# StrainGuageNode.net
KiCad netlist of a schematic drawn in Altium Designer
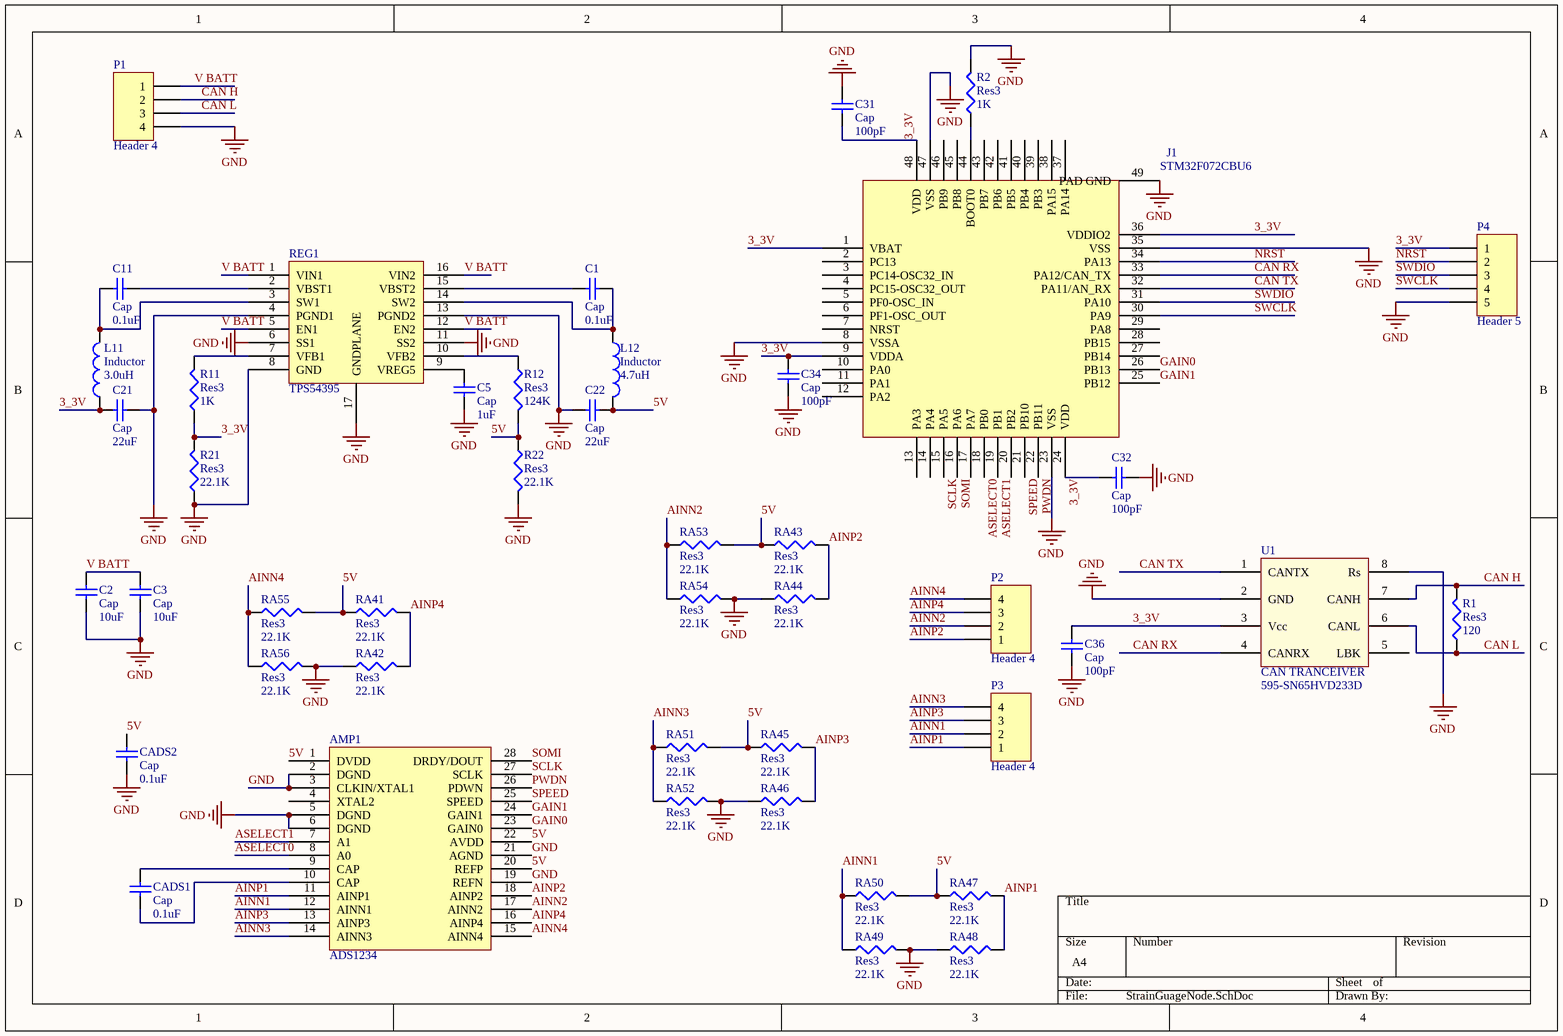
[diagram p0: StrainGuageNode.SchDoc]

(export (version "E")
  (design (tool "Eeschema 10.0.6"))
  (components
    (comp (ref "AMP1")
      (value "ADS1234")
      (footprint "ADS1234")
      (libsource (lib "StrainGaugeLib") (part "ADS1234"))
    )
    (comp (ref "C1")
      (value "Cap")
      (footprint "R0805")
      (description "Capacitor")
      (fields (field (name "ALTIUM_VALUE") "0.1uF") (field (name "PUBLISHER") "Altium Limited"))
      (libsource (lib "Miscellaneous Devices") (part "Cap"))
    )
    (comp (ref "C2")
      (value "Cap")
      (footprint "R0805")
      (description "Capacitor")
      (fields (field (name "ALTIUM_VALUE") "10uF") (field (name "PUBLISHER") "Altium Limited"))
      (libsource (lib "Miscellaneous Devices") (part "Cap"))
    )
    (comp (ref "C3")
      (value "Cap")
      (footprint "R0805")
      (description "Capacitor")
      (fields (field (name "ALTIUM_VALUE") "10uF") (field (name "PUBLISHER") "Altium Limited"))
      (libsource (lib "Miscellaneous Devices") (part "Cap"))
    )
    (comp (ref "C5")
      (value "Cap")
      (footprint "R0805")
      (description "Capacitor")
      (fields (field (name "ALTIUM_VALUE") "1uF") (field (name "PUBLISHER") "Altium Limited"))
      (libsource (lib "Miscellaneous Devices") (part "Cap"))
    )
    (comp (ref "C11")
      (value "Cap")
      (footprint "R0805")
      (description "Capacitor")
      (fields (field (name "ALTIUM_VALUE") "0.1uF") (field (name "PUBLISHER") "Altium Limited"))
      (libsource (lib "Miscellaneous Devices") (part "Cap"))
    )
    (comp (ref "C21")
      (value "Cap")
      (footprint "R0805")
      (description "Capacitor")
      (fields (field (name "ALTIUM_VALUE") "22uF") (field (name "PUBLISHER") "Altium Limited"))
      (libsource (lib "Miscellaneous Devices") (part "Cap"))
    )
    (comp (ref "C22")
      (value "Cap")
      (footprint "R0805")
      (description "Capacitor")
      (fields (field (name "ALTIUM_VALUE") "22uF") (field (name "PUBLISHER") "Altium Limited"))
      (libsource (lib "Miscellaneous Devices") (part "Cap"))
    )
    (comp (ref "C31")
      (value "Cap")
      (footprint "R0805")
      (description "Capacitor")
      (fields (field (name "ALTIUM_VALUE") "100pF") (field (name "PUBLISHER") "Altium Limited"))
      (libsource (lib "Miscellaneous Devices") (part "Cap"))
    )
    (comp (ref "C32")
      (value "Cap")
      (footprint "R0805")
      (description "Capacitor")
      (fields (field (name "ALTIUM_VALUE") "100pF") (field (name "PUBLISHER") "Altium Limited"))
      (libsource (lib "Miscellaneous Devices") (part "Cap"))
    )
    (comp (ref "C34")
      (value "Cap")
      (footprint "R0805")
      (description "Capacitor")
      (fields (field (name "ALTIUM_VALUE") "100pF") (field (name "PUBLISHER") "Altium Limited"))
      (libsource (lib "Miscellaneous Devices") (part "Cap"))
    )
    (comp (ref "C36")
      (value "Cap")
      (footprint "R0805")
      (description "Capacitor")
      (fields (field (name "ALTIUM_VALUE") "100pF") (field (name "PUBLISHER") "Altium Limited"))
      (libsource (lib "Miscellaneous Devices") (part "Cap"))
    )
    (comp (ref "CADS1")
      (value "Cap")
      (footprint "R0805")
      (description "Capacitor")
      (fields (field (name "ALTIUM_VALUE") "0.1uF") (field (name "PUBLISHER") "Altium Limited"))
      (libsource (lib "Miscellaneous Devices") (part "Cap"))
    )
    (comp (ref "CADS2")
      (value "Cap")
      (footprint "R0805")
      (description "Capacitor")
      (fields (field (name "ALTIUM_VALUE") "0.1uF") (field (name "PUBLISHER") "Altium Limited"))
      (libsource (lib "Miscellaneous Devices") (part "Cap"))
    )
    (comp (ref "J1")
      (value "STM32F072CBU6")
      (footprint "STM32F072CBU6 - duplicate")
      (description "MICROCONTROLLER")
      (libsource (lib "CAN_Node") (part "STM32F072CBU6"))
    )
    (comp (ref "L11")
      (value "Inductor")
      (footprint "Inductor")
      (fields (field (name "ALTIUM_VALUE") "3.0uH") (field (name "PUBLISHER") "Altium Limited"))
      (libsource (lib "") (part "Inductor_1"))
    )
    (comp (ref "L12")
      (value "Inductor")
      (footprint "Inductor")
      (fields (field (name "ALTIUM_VALUE") "4.7uH") (field (name "PUBLISHER") "Altium Limited"))
      (libsource (lib "Miscellaneous Devices") (part "Inductor"))
    )
    (comp (ref "P1")
      (value "Header 4")
      (footprint "HDR1X4")
      (description "Header, 4-Pin")
      (fields (field (name "PUBLISHER") "Altium Limited"))
      (libsource (lib "") (part "Header 4_1"))
    )
    (comp (ref "P2")
      (value "Header 4")
      (footprint "HDR1X4")
      (description "Header, 4-Pin")
      (fields (field (name "PUBLISHER") "Altium Limited"))
      (libsource (lib "Miscellaneous Connectors") (part "Header 4"))
    )
    (comp (ref "P3")
      (value "Header 4")
      (footprint "HDR1X4")
      (description "Header, 4-Pin")
      (fields (field (name "PUBLISHER") "Altium Limited"))
      (libsource (lib "Miscellaneous Connectors") (part "Header 4"))
    )
    (comp (ref "P4")
      (value "Header 5")
      (footprint "HDR1X5")
      (description "Header, 5-Pin")
      (fields (field (name "PUBLISHER") "Altium Limited"))
      (libsource (lib "Miscellaneous Connectors") (part "Header 5"))
    )
    (comp (ref "R1")
      (value "Res3")
      (footprint "R0805")
      (description "Resistor")
      (fields (field (name "ALTIUM_VALUE") "120") (field (name "PUBLISHER") "Altium Limited"))
      (libsource (lib "Miscellaneous Devices") (part "Res3"))
    )
    (comp (ref "R2")
      (value "Res3")
      (footprint "R0805")
      (description "Resistor")
      (fields (field (name "ALTIUM_VALUE") "1K") (field (name "PUBLISHER") "Altium Limited"))
      (libsource (lib "Miscellaneous Devices") (part "Res3"))
    )
    (comp (ref "R11")
      (value "Res3")
      (footprint "R0805")
      (description "Resistor")
      (fields (field (name "ALTIUM_VALUE") "1K") (field (name "PUBLISHER") "Altium Limited"))
      (libsource (lib "Miscellaneous Devices") (part "Res3"))
    )
    (comp (ref "R12")
      (value "Res3")
      (footprint "R0805")
      (description "Resistor")
      (fields (field (name "ALTIUM_VALUE") "124K") (field (name "PUBLISHER") "Altium Limited"))
      (libsource (lib "Miscellaneous Devices") (part "Res3"))
    )
    (comp (ref "R21")
      (value "Res3")
      (footprint "R0805")
      (description "Resistor")
      (fields (field (name "ALTIUM_VALUE") "22.1K") (field (name "PUBLISHER") "Altium Limited"))
      (libsource (lib "Miscellaneous Devices") (part "Res3"))
    )
    (comp (ref "R22")
      (value "Res3")
      (footprint "R0805")
      (description "Resistor")
      (fields (field (name "ALTIUM_VALUE") "22.1K") (field (name "PUBLISHER") "Altium Limited"))
      (libsource (lib "Miscellaneous Devices") (part "Res3"))
    )
    (comp (ref "RA41")
      (value "Res3")
      (footprint "R0805")
      (description "Resistor")
      (fields (field (name "ALTIUM_VALUE") "22.1K") (field (name "PUBLISHER") "Altium Limited"))
      (libsource (lib "Miscellaneous Devices") (part "Res3"))
    )
    (comp (ref "RA42")
      (value "Res3")
      (footprint "R0805")
      (description "Resistor")
      (fields (field (name "ALTIUM_VALUE") "22.1K") (field (name "PUBLISHER") "Altium Limited"))
      (libsource (lib "Miscellaneous Devices") (part "Res3"))
    )
    (comp (ref "RA43")
      (value "Res3")
      (footprint "R0805")
      (description "Resistor")
      (fields (field (name "ALTIUM_VALUE") "22.1K") (field (name "PUBLISHER") "Altium Limited"))
      (libsource (lib "Miscellaneous Devices") (part "Res3"))
    )
    (comp (ref "RA44")
      (value "Res3")
      (footprint "R0805")
      (description "Resistor")
      (fields (field (name "ALTIUM_VALUE") "22.1K") (field (name "PUBLISHER") "Altium Limited"))
      (libsource (lib "Miscellaneous Devices") (part "Res3"))
    )
    (comp (ref "RA45")
      (value "Res3")
      (footprint "R0805")
      (description "Resistor")
      (fields (field (name "ALTIUM_VALUE") "22.1K") (field (name "PUBLISHER") "Altium Limited"))
      (libsource (lib "Miscellaneous Devices") (part "Res3"))
    )
    (comp (ref "RA46")
      (value "Res3")
      (footprint "R0805")
      (description "Resistor")
      (fields (field (name "ALTIUM_VALUE") "22.1K") (field (name "PUBLISHER") "Altium Limited"))
      (libsource (lib "Miscellaneous Devices") (part "Res3"))
    )
    (comp (ref "RA47")
      (value "Res3")
      (footprint "R0805")
      (description "Resistor")
      (fields (field (name "ALTIUM_VALUE") "22.1K") (field (name "PUBLISHER") "Altium Limited"))
      (libsource (lib "Miscellaneous Devices") (part "Res3"))
    )
    (comp (ref "RA48")
      (value "Res3")
      (footprint "R0805")
      (description "Resistor")
      (fields (field (name "ALTIUM_VALUE") "22.1K") (field (name "PUBLISHER") "Altium Limited"))
      (libsource (lib "Miscellaneous Devices") (part "Res3"))
    )
    (comp (ref "RA49")
      (value "Res3")
      (footprint "R0805")
      (description "Resistor")
      (fields (field (name "ALTIUM_VALUE") "22.1K") (field (name "PUBLISHER") "Altium Limited"))
      (libsource (lib "Miscellaneous Devices") (part "Res3"))
    )
    (comp (ref "RA50")
      (value "Res3")
      (footprint "R0805")
      (description "Resistor")
      (fields (field (name "ALTIUM_VALUE") "22.1K") (field (name "PUBLISHER") "Altium Limited"))
      (libsource (lib "Miscellaneous Devices") (part "Res3"))
    )
    (comp (ref "RA51")
      (value "Res3")
      (footprint "R0805")
      (description "Resistor")
      (fields (field (name "ALTIUM_VALUE") "22.1K") (field (name "PUBLISHER") "Altium Limited"))
      (libsource (lib "Miscellaneous Devices") (part "Res3"))
    )
    (comp (ref "RA52")
      (value "Res3")
      (footprint "R0805")
      (description "Resistor")
      (fields (field (name "ALTIUM_VALUE") "22.1K") (field (name "PUBLISHER") "Altium Limited"))
      (libsource (lib "Miscellaneous Devices") (part "Res3"))
    )
    (comp (ref "RA53")
      (value "Res3")
      (footprint "R0805")
      (description "Resistor")
      (fields (field (name "ALTIUM_VALUE") "22.1K") (field (name "PUBLISHER") "Altium Limited"))
      (libsource (lib "Miscellaneous Devices") (part "Res3"))
    )
    (comp (ref "RA54")
      (value "Res3")
      (footprint "R0805")
      (description "Resistor")
      (fields (field (name "ALTIUM_VALUE") "22.1K") (field (name "PUBLISHER") "Altium Limited"))
      (libsource (lib "Miscellaneous Devices") (part "Res3"))
    )
    (comp (ref "RA55")
      (value "Res3")
      (footprint "R0805")
      (description "Resistor")
      (fields (field (name "ALTIUM_VALUE") "22.1K") (field (name "PUBLISHER") "Altium Limited"))
      (libsource (lib "Miscellaneous Devices") (part "Res3"))
    )
    (comp (ref "RA56")
      (value "Res3")
      (footprint "R0805")
      (description "Resistor")
      (fields (field (name "ALTIUM_VALUE") "22.1K") (field (name "PUBLISHER") "Altium Limited"))
      (libsource (lib "Miscellaneous Devices") (part "Res3"))
    )
    (comp (ref "REG1")
      (value "TPS54395")
      (footprint "TPS54395")
      (description "Dual Channel Buck Converter")
      (libsource (lib "StrainGaugeLib") (part "TPS54395"))
    )
    (comp (ref "U1")
      (value "CAN TRANCEIVER")
      (footprint "SOP8")
      (fields (field (name "SUPPLIER PART NUMBER 1") "595-SN65HVD233D"))
      (libsource (lib "CAN_Node") (part "595-SN65HVD233"))
    )
  )
  (nets
    (net (code "1") (name "/3_3V") (class "Default")
      (node (ref "C21") (pin "2") (pinfunction "2_2") (pintype "passive"))
      (node (ref "C31") (pin "2") (pinfunction "2_2") (pintype "passive"))
      (node (ref "C32") (pin "2") (pinfunction "2_2") (pintype "passive"))
      (node (ref "C34") (pin "2") (pinfunction "2_2") (pintype "passive"))
      (node (ref "C36") (pin "2") (pinfunction "2_2") (pintype "passive"))
      (node (ref "J1") (pin "1") (pinfunction "VBAT_1") (pintype "passive"))
      (node (ref "J1") (pin "24") (pinfunction "VDD_24") (pintype "passive"))
      (node (ref "J1") (pin "36") (pinfunction "VDDIO2_36") (pintype "passive"))
      (node (ref "J1") (pin "48") (pinfunction "VDD_48") (pintype "passive"))
      (node (ref "J1") (pin "9") (pinfunction "VDDA_9") (pintype "passive"))
      (node (ref "L11") (pin "1") (pinfunction "1_1") (pintype "passive"))
      (node (ref "P4") (pin "1") (pinfunction "1_1") (pintype "passive"))
      (node (ref "R11") (pin "1") (pinfunction "1_1") (pintype "passive"))
      (node (ref "R21") (pin "2") (pinfunction "2_2") (pintype "passive"))
      (node (ref "U1") (pin "3") (pinfunction "Vcc_3") (pintype "passive"))
    )
    (net (code "2") (name "/5V") (class "Default")
      (node (ref "AMP1") (pin "1") (pinfunction "DVDD_1") (pintype "passive"))
      (node (ref "AMP1") (pin "20") (pinfunction "REFP_20") (pintype "passive"))
      (node (ref "AMP1") (pin "22") (pinfunction "AVDD_22") (pintype "passive"))
      (node (ref "C22") (pin "2") (pinfunction "2_2") (pintype "passive"))
      (node (ref "CADS2") (pin "1") (pinfunction "1_1") (pintype "passive"))
      (node (ref "L12") (pin "1") (pinfunction "1_1") (pintype "passive"))
      (node (ref "R12") (pin "1") (pinfunction "1_1") (pintype "passive"))
      (node (ref "R22") (pin "2") (pinfunction "2_2") (pintype "passive"))
      (node (ref "RA41") (pin "2") (pinfunction "2_2") (pintype "passive"))
      (node (ref "RA43") (pin "2") (pinfunction "2_2") (pintype "passive"))
      (node (ref "RA45") (pin "2") (pinfunction "2_2") (pintype "passive"))
      (node (ref "RA47") (pin "2") (pinfunction "2_2") (pintype "passive"))
      (node (ref "RA50") (pin "1") (pinfunction "1_1") (pintype "passive"))
      (node (ref "RA51") (pin "1") (pinfunction "1_1") (pintype "passive"))
      (node (ref "RA53") (pin "1") (pinfunction "1_1") (pintype "passive"))
      (node (ref "RA55") (pin "1") (pinfunction "1_1") (pintype "passive"))
    )
    (net (code "3") (name "/AINN1") (class "Default")
      (node (ref "AMP1") (pin "12") (pinfunction "AINN1_12") (pintype "passive"))
      (node (ref "P3") (pin "2") (pinfunction "2_2") (pintype "passive"))
      (node (ref "RA49") (pin "2") (pinfunction "2_2") (pintype "passive"))
      (node (ref "RA50") (pin "2") (pinfunction "2_2") (pintype "passive"))
    )
    (net (code "4") (name "/AINN2") (class "Default")
      (node (ref "AMP1") (pin "17") (pinfunction "AINN2_17") (pintype "passive"))
      (node (ref "P2") (pin "2") (pinfunction "2_2") (pintype "passive"))
      (node (ref "RA53") (pin "2") (pinfunction "2_2") (pintype "passive"))
      (node (ref "RA54") (pin "2") (pinfunction "2_2") (pintype "passive"))
    )
    (net (code "5") (name "/AINN3") (class "Default")
      (node (ref "AMP1") (pin "14") (pinfunction "AINN3_14") (pintype "passive"))
      (node (ref "P3") (pin "4") (pinfunction "4_4") (pintype "passive"))
      (node (ref "RA51") (pin "2") (pinfunction "2_2") (pintype "passive"))
      (node (ref "RA52") (pin "2") (pinfunction "2_2") (pintype "passive"))
    )
    (net (code "6") (name "/AINN4") (class "Default")
      (node (ref "AMP1") (pin "15") (pinfunction "AINN4_15") (pintype "passive"))
      (node (ref "P2") (pin "4") (pinfunction "4_4") (pintype "passive"))
      (node (ref "RA55") (pin "2") (pinfunction "2_2") (pintype "passive"))
      (node (ref "RA56") (pin "2") (pinfunction "2_2") (pintype "passive"))
    )
    (net (code "7") (name "/AINP1") (class "Default")
      (node (ref "AMP1") (pin "11") (pinfunction "AINP1_11") (pintype "passive"))
      (node (ref "P3") (pin "1") (pinfunction "1_1") (pintype "passive"))
      (node (ref "RA47") (pin "1") (pinfunction "1_1") (pintype "passive"))
      (node (ref "RA48") (pin "1") (pinfunction "1_1") (pintype "passive"))
    )
    (net (code "8") (name "/AINP2") (class "Default")
      (node (ref "AMP1") (pin "18") (pinfunction "AINP2_18") (pintype "passive"))
      (node (ref "P2") (pin "1") (pinfunction "1_1") (pintype "passive"))
      (node (ref "RA43") (pin "1") (pinfunction "1_1") (pintype "passive"))
      (node (ref "RA44") (pin "1") (pinfunction "1_1") (pintype "passive"))
    )
    (net (code "9") (name "/AINP3") (class "Default")
      (node (ref "AMP1") (pin "13") (pinfunction "AINP3_13") (pintype "passive"))
      (node (ref "P3") (pin "3") (pinfunction "3_3") (pintype "passive"))
      (node (ref "RA45") (pin "1") (pinfunction "1_1") (pintype "passive"))
      (node (ref "RA46") (pin "1") (pinfunction "1_1") (pintype "passive"))
    )
    (net (code "10") (name "/AINP4") (class "Default")
      (node (ref "AMP1") (pin "16") (pinfunction "AINP4_16") (pintype "passive"))
      (node (ref "P2") (pin "3") (pinfunction "3_3") (pintype "passive"))
      (node (ref "RA41") (pin "1") (pinfunction "1_1") (pintype "passive"))
      (node (ref "RA42") (pin "1") (pinfunction "1_1") (pintype "passive"))
    )
    (net (code "11") (name "/ASELECT0") (class "Default")
      (node (ref "AMP1") (pin "8") (pinfunction "A0_8") (pintype "passive"))
      (node (ref "J1") (pin "18") (pinfunction "PB0_18") (pintype "passive"))
    )
    (net (code "12") (name "/ASELECT1") (class "Default")
      (node (ref "AMP1") (pin "7") (pinfunction "A1_7") (pintype "passive"))
      (node (ref "J1") (pin "19") (pinfunction "PB1_19") (pintype "passive"))
    )
    (net (code "13") (name "/CAN H") (class "Default")
      (node (ref "P1") (pin "2") (pinfunction "2_2") (pintype "passive"))
      (node (ref "R1") (pin "2") (pinfunction "2_2") (pintype "passive"))
      (node (ref "U1") (pin "7") (pinfunction "CANH_7") (pintype "passive"))
    )
    (net (code "14") (name "/CAN L") (class "Default")
      (node (ref "P1") (pin "3") (pinfunction "3_3") (pintype "passive"))
      (node (ref "R1") (pin "1") (pinfunction "1_1") (pintype "passive"))
      (node (ref "U1") (pin "6") (pinfunction "CANL_6") (pintype "passive"))
    )
    (net (code "15") (name "/CAN RX") (class "Default")
      (node (ref "J1") (pin "33") (pinfunction "PA12/CAN_TX_33") (pintype "passive"))
      (node (ref "U1") (pin "4") (pinfunction "CANRX_4") (pintype "passive"))
    )
    (net (code "16") (name "/CAN TX") (class "Default")
      (node (ref "J1") (pin "32") (pinfunction "PA11/AN_RX_32") (pintype "passive"))
      (node (ref "U1") (pin "1") (pinfunction "CANTX_1") (pintype "passive"))
    )
    (net (code "17") (name "/GAIN0") (class "Default")
      (node (ref "AMP1") (pin "23") (pinfunction "GAIN0_23") (pintype "passive"))
      (node (ref "J1") (pin "26") (pinfunction "PB13_26") (pintype "passive"))
    )
    (net (code "18") (name "/GAIN1") (class "Default")
      (node (ref "AMP1") (pin "24") (pinfunction "GAIN1_24") (pintype "passive"))
      (node (ref "J1") (pin "25") (pinfunction "PB12_25") (pintype "passive"))
    )
    (net (code "19") (name "/NRST") (class "Default")
      (node (ref "J1") (pin "34") (pinfunction "PA13_34") (pintype "passive"))
      (node (ref "P4") (pin "2") (pinfunction "2_2") (pintype "passive"))
    )
    (net (code "20") (name "/PWDN") (class "Default")
      (node (ref "AMP1") (pin "26") (pinfunction "PDWN_26") (pintype "passive"))
      (node (ref "J1") (pin "22") (pinfunction "PB11_22") (pintype "passive"))
    )
    (net (code "21") (name "/SCLK") (class "Default")
      (node (ref "AMP1") (pin "27") (pinfunction "SCLK_27") (pintype "passive"))
      (node (ref "J1") (pin "15") (pinfunction "PA5_15") (pintype "passive"))
    )
    (net (code "22") (name "/SOMI") (class "Default")
      (node (ref "AMP1") (pin "28") (pinfunction "DRDY/DOUT_28") (pintype "passive"))
      (node (ref "J1") (pin "16") (pinfunction "PA6_16") (pintype "passive"))
    )
    (net (code "23") (name "/SPEED") (class "Default")
      (node (ref "AMP1") (pin "25") (pinfunction "SPEED_25") (pintype "passive"))
      (node (ref "J1") (pin "21") (pinfunction "PB10_21") (pintype "passive"))
    )
    (net (code "24") (name "/SWCLK") (class "Default")
      (node (ref "J1") (pin "30") (pinfunction "PA9_30") (pintype "passive"))
      (node (ref "P4") (pin "4") (pinfunction "4_4") (pintype "passive"))
    )
    (net (code "25") (name "/SWDIO") (class "Default")
      (node (ref "J1") (pin "31") (pinfunction "PA10_31") (pintype "passive"))
      (node (ref "P4") (pin "3") (pinfunction "3_3") (pintype "passive"))
    )
    (net (code "26") (name "/V BATT") (class "Default")
      (node (ref "C2") (pin "1") (pinfunction "1_1") (pintype "passive"))
      (node (ref "C3") (pin "1") (pinfunction "1_1") (pintype "passive"))
      (node (ref "P1") (pin "1") (pinfunction "1_1") (pintype "passive"))
      (node (ref "REG1") (pin "1") (pinfunction "VIN1_1") (pintype "passive"))
      (node (ref "REG1") (pin "12") (pinfunction "EN2_12") (pintype "passive"))
      (node (ref "REG1") (pin "16") (pinfunction "VIN2_16") (pintype "passive"))
      (node (ref "REG1") (pin "5") (pinfunction "EN1_5") (pintype "passive"))
    )
    (net (code "27") (name "GND") (class "Default")
      (node (ref "AMP1") (pin "19") (pinfunction "REFN_19") (pintype "passive"))
      (node (ref "AMP1") (pin "2") (pinfunction "DGND_2") (pintype "passive"))
      (node (ref "AMP1") (pin "21") (pinfunction "AGND_21") (pintype "passive"))
      (node (ref "AMP1") (pin "3") (pinfunction "CLKIN/XTAL1_3") (pintype "passive"))
      (node (ref "AMP1") (pin "5") (pinfunction "DGND_5") (pintype "passive"))
      (node (ref "AMP1") (pin "6") (pinfunction "DGND_6") (pintype "passive"))
      (node (ref "C2") (pin "2") (pinfunction "2_2") (pintype "passive"))
      (node (ref "C21") (pin "1") (pinfunction "1_1") (pintype "passive"))
      (node (ref "C22") (pin "1") (pinfunction "1_1") (pintype "passive"))
      (node (ref "C3") (pin "2") (pinfunction "2_2") (pintype "passive"))
      (node (ref "C31") (pin "1") (pinfunction "1_1") (pintype "passive"))
      (node (ref "C32") (pin "1") (pinfunction "1_1") (pintype "passive"))
      (node (ref "C34") (pin "1") (pinfunction "1_1") (pintype "passive"))
      (node (ref "C36") (pin "1") (pinfunction "1_1") (pintype "passive"))
      (node (ref "C5") (pin "2") (pinfunction "2_2") (pintype "passive"))
      (node (ref "CADS2") (pin "2") (pinfunction "2_2") (pintype "passive"))
      (node (ref "J1") (pin "23") (pinfunction "VSS_23") (pintype "passive"))
      (node (ref "J1") (pin "35") (pinfunction "VSS_35") (pintype "passive"))
      (node (ref "J1") (pin "47") (pinfunction "VSS_47") (pintype "passive"))
      (node (ref "J1") (pin "49") (pinfunction "PAD_GND_49") (pintype "passive"))
      (node (ref "J1") (pin "8") (pinfunction "VSSA_8") (pintype "passive"))
      (node (ref "P1") (pin "4") (pinfunction "4_4") (pintype "passive"))
      (node (ref "P4") (pin "5") (pinfunction "5_5") (pintype "passive"))
      (node (ref "R2") (pin "2") (pinfunction "2_2") (pintype "passive"))
      (node (ref "R21") (pin "1") (pinfunction "1_1") (pintype "passive"))
      (node (ref "R22") (pin "1") (pinfunction "1_1") (pintype "passive"))
      (node (ref "RA42") (pin "2") (pinfunction "2_2") (pintype "passive"))
      (node (ref "RA44") (pin "2") (pinfunction "2_2") (pintype "passive"))
      (node (ref "RA46") (pin "2") (pinfunction "2_2") (pintype "passive"))
      (node (ref "RA48") (pin "2") (pinfunction "2_2") (pintype "passive"))
      (node (ref "RA49") (pin "1") (pinfunction "1_1") (pintype "passive"))
      (node (ref "RA52") (pin "1") (pinfunction "1_1") (pintype "passive"))
      (node (ref "RA54") (pin "1") (pinfunction "1_1") (pintype "passive"))
      (node (ref "RA56") (pin "1") (pinfunction "1_1") (pintype "passive"))
      (node (ref "REG1") (pin "11") (pinfunction "SS2_11") (pintype "passive"))
      (node (ref "REG1") (pin "13") (pinfunction "PGND2_13") (pintype "passive"))
      (node (ref "REG1") (pin "17") (pinfunction "GNDPLANE_17") (pintype "passive"))
      (node (ref "REG1") (pin "4") (pinfunction "PGND1_4") (pintype "passive"))
      (node (ref "REG1") (pin "6") (pinfunction "SS1_6") (pintype "passive"))
      (node (ref "REG1") (pin "8") (pinfunction "GND_8") (pintype "passive"))
      (node (ref "U1") (pin "2") (pinfunction "GND_2") (pintype "passive"))
      (node (ref "U1") (pin "8") (pinfunction "Rs_8") (pintype "passive"))
    )
    (net (code "28") (name "Net-(AMP1-CAP-Pad9)") (class "Default")
      (node (ref "AMP1") (pin "9") (pinfunction "CAP_9") (pintype "passive"))
      (node (ref "CADS1") (pin "2") (pinfunction "2_2") (pintype "passive"))
    )
    (net (code "29") (name "Net-(AMP1-CAP-Pad10)") (class "Default")
      (node (ref "AMP1") (pin "10") (pinfunction "CAP_10") (pintype "passive"))
      (node (ref "CADS1") (pin "1") (pinfunction "1_1") (pintype "passive"))
    )
    (net (code "30") (name "Net-(J1-BOOT0)") (class "Default")
      (node (ref "J1") (pin "44") (pinfunction "BOOT0_44") (pintype "passive"))
      (node (ref "R2") (pin "1") (pinfunction "1_1") (pintype "passive"))
    )
    (net (code "31") (name "Net-(REG1-SW1)") (class "Default")
      (node (ref "C11") (pin "2") (pinfunction "2_2") (pintype "passive"))
      (node (ref "L11") (pin "2") (pinfunction "2_2") (pintype "passive"))
      (node (ref "REG1") (pin "3") (pinfunction "SW1_3") (pintype "passive"))
    )
    (net (code "32") (name "Net-(REG1-SW2)") (class "Default")
      (node (ref "C1") (pin "2") (pinfunction "2_2") (pintype "passive"))
      (node (ref "L12") (pin "2") (pinfunction "2_2") (pintype "passive"))
      (node (ref "REG1") (pin "14") (pinfunction "SW2_14") (pintype "passive"))
    )
    (net (code "33") (name "Net-(REG1-VBST1)") (class "Default")
      (node (ref "C11") (pin "1") (pinfunction "1_1") (pintype "passive"))
      (node (ref "REG1") (pin "2") (pinfunction "VBST1_2") (pintype "passive"))
    )
    (net (code "34") (name "Net-(REG1-VBST2)") (class "Default")
      (node (ref "C1") (pin "1") (pinfunction "1_1") (pintype "passive"))
      (node (ref "REG1") (pin "15") (pinfunction "VBST2_15") (pintype "passive"))
    )
    (net (code "35") (name "Net-(REG1-VFB1)") (class "Default")
      (node (ref "R11") (pin "2") (pinfunction "2_2") (pintype "passive"))
      (node (ref "REG1") (pin "7") (pinfunction "VFB1_7") (pintype "passive"))
    )
    (net (code "36") (name "Net-(REG1-VFB2)") (class "Default")
      (node (ref "R12") (pin "2") (pinfunction "2_2") (pintype "passive"))
      (node (ref "REG1") (pin "10") (pinfunction "VFB2_10") (pintype "passive"))
    )
    (net (code "37") (name "Net-(REG1-VREG5)") (class "Default")
      (node (ref "C5") (pin "1") (pinfunction "1_1") (pintype "passive"))
      (node (ref "REG1") (pin "9") (pinfunction "VREG5_9") (pintype "passive"))
    )
    (net (code "38") (name "unconnected-(AMP1-XTAL2-Pad4)") (class "Default")
      (node (ref "AMP1") (pin "4") (pinfunction "XTAL2_4") (pintype "passive"))
    )
    (net (code "39") (name "unconnected-(J1-NRST-Pad7)") (class "Default")
      (node (ref "J1") (pin "7") (pinfunction "NRST_7") (pintype "passive"))
    )
    (net (code "40") (name "unconnected-(J1-PA0-Pad10)") (class "Default")
      (node (ref "J1") (pin "10") (pinfunction "PA0_10") (pintype "passive"))
    )
    (net (code "41") (name "unconnected-(J1-PA1-Pad11)") (class "Default")
      (node (ref "J1") (pin "11") (pinfunction "PA1_11") (pintype "passive"))
    )
    (net (code "42") (name "unconnected-(J1-PA2-Pad12)") (class "Default")
      (node (ref "J1") (pin "12") (pinfunction "PA2_12") (pintype "passive"))
    )
    (net (code "43") (name "unconnected-(J1-PA3-Pad13)") (class "Default")
      (node (ref "J1") (pin "13") (pinfunction "PA3_13") (pintype "passive"))
    )
    (net (code "44") (name "unconnected-(J1-PA4-Pad14)") (class "Default")
      (node (ref "J1") (pin "14") (pinfunction "PA4_14") (pintype "passive"))
    )
    (net (code "45") (name "unconnected-(J1-PA7-Pad17)") (class "Default")
      (node (ref "J1") (pin "17") (pinfunction "PA7_17") (pintype "passive"))
    )
    (net (code "46") (name "unconnected-(J1-PA8-Pad29)") (class "Default")
      (node (ref "J1") (pin "29") (pinfunction "PA8_29") (pintype "passive"))
    )
    (net (code "47") (name "unconnected-(J1-PA14-Pad37)") (class "Default")
      (node (ref "J1") (pin "37") (pinfunction "PA14_37") (pintype "passive"))
    )
    (net (code "48") (name "unconnected-(J1-PA15-Pad38)") (class "Default")
      (node (ref "J1") (pin "38") (pinfunction "PA15_38") (pintype "passive"))
    )
    (net (code "49") (name "unconnected-(J1-PB2-Pad20)") (class "Default")
      (node (ref "J1") (pin "20") (pinfunction "PB2_20") (pintype "passive"))
    )
    (net (code "50") (name "unconnected-(J1-PB3-Pad39)") (class "Default")
      (node (ref "J1") (pin "39") (pinfunction "PB3_39") (pintype "passive"))
    )
    (net (code "51") (name "unconnected-(J1-PB4-Pad40)") (class "Default")
      (node (ref "J1") (pin "40") (pinfunction "PB4_40") (pintype "passive"))
    )
    (net (code "52") (name "unconnected-(J1-PB5-Pad41)") (class "Default")
      (node (ref "J1") (pin "41") (pinfunction "PB5_41") (pintype "passive"))
    )
    (net (code "53") (name "unconnected-(J1-PB6-Pad42)") (class "Default")
      (node (ref "J1") (pin "42") (pinfunction "PB6_42") (pintype "passive"))
    )
    (net (code "54") (name "unconnected-(J1-PB7-Pad43)") (class "Default")
      (node (ref "J1") (pin "43") (pinfunction "PB7_43") (pintype "passive"))
    )
    (net (code "55") (name "unconnected-(J1-PB8-Pad45)") (class "Default")
      (node (ref "J1") (pin "45") (pinfunction "PB8_45") (pintype "passive"))
    )
    (net (code "56") (name "unconnected-(J1-PB9-Pad46)") (class "Default")
      (node (ref "J1") (pin "46") (pinfunction "PB9_46") (pintype "passive"))
    )
    (net (code "57") (name "unconnected-(J1-PB14-Pad27)") (class "Default")
      (node (ref "J1") (pin "27") (pinfunction "PB14_27") (pintype "passive"))
    )
    (net (code "58") (name "unconnected-(J1-PB15-Pad28)") (class "Default")
      (node (ref "J1") (pin "28") (pinfunction "PB15_28") (pintype "passive"))
    )
    (net (code "59") (name "unconnected-(J1-PC13-Pad2)") (class "Default")
      (node (ref "J1") (pin "2") (pinfunction "PC13_2") (pintype "passive"))
    )
    (net (code "60") (name "unconnected-(J1-PC14-OSC32_IN-Pad3)") (class "Default")
      (node (ref "J1") (pin "3") (pinfunction "PC14-OSC32_IN_3") (pintype "passive"))
    )
    (net (code "61") (name "unconnected-(J1-PC15-OSC32_OUT-Pad4)") (class "Default")
      (node (ref "J1") (pin "4") (pinfunction "PC15-OSC32_OUT_4") (pintype "passive"))
    )
    (net (code "62") (name "unconnected-(J1-PF0-OSC_IN-Pad5)") (class "Default")
      (node (ref "J1") (pin "5") (pinfunction "PF0-OSC_IN_5") (pintype "passive"))
    )
    (net (code "63") (name "unconnected-(J1-PF1-OSC_OUT-Pad6)") (class "Default")
      (node (ref "J1") (pin "6") (pinfunction "PF1-OSC_OUT_6") (pintype "passive"))
    )
    (net (code "64") (name "unconnected-(U1-LBK-Pad5)") (class "Default")
      (node (ref "U1") (pin "5") (pinfunction "LBK_5") (pintype "passive"))
    )
  )
)
